# PartsHunter_Slave.net
KiCad netlist of a schematic drawn in EAGLE
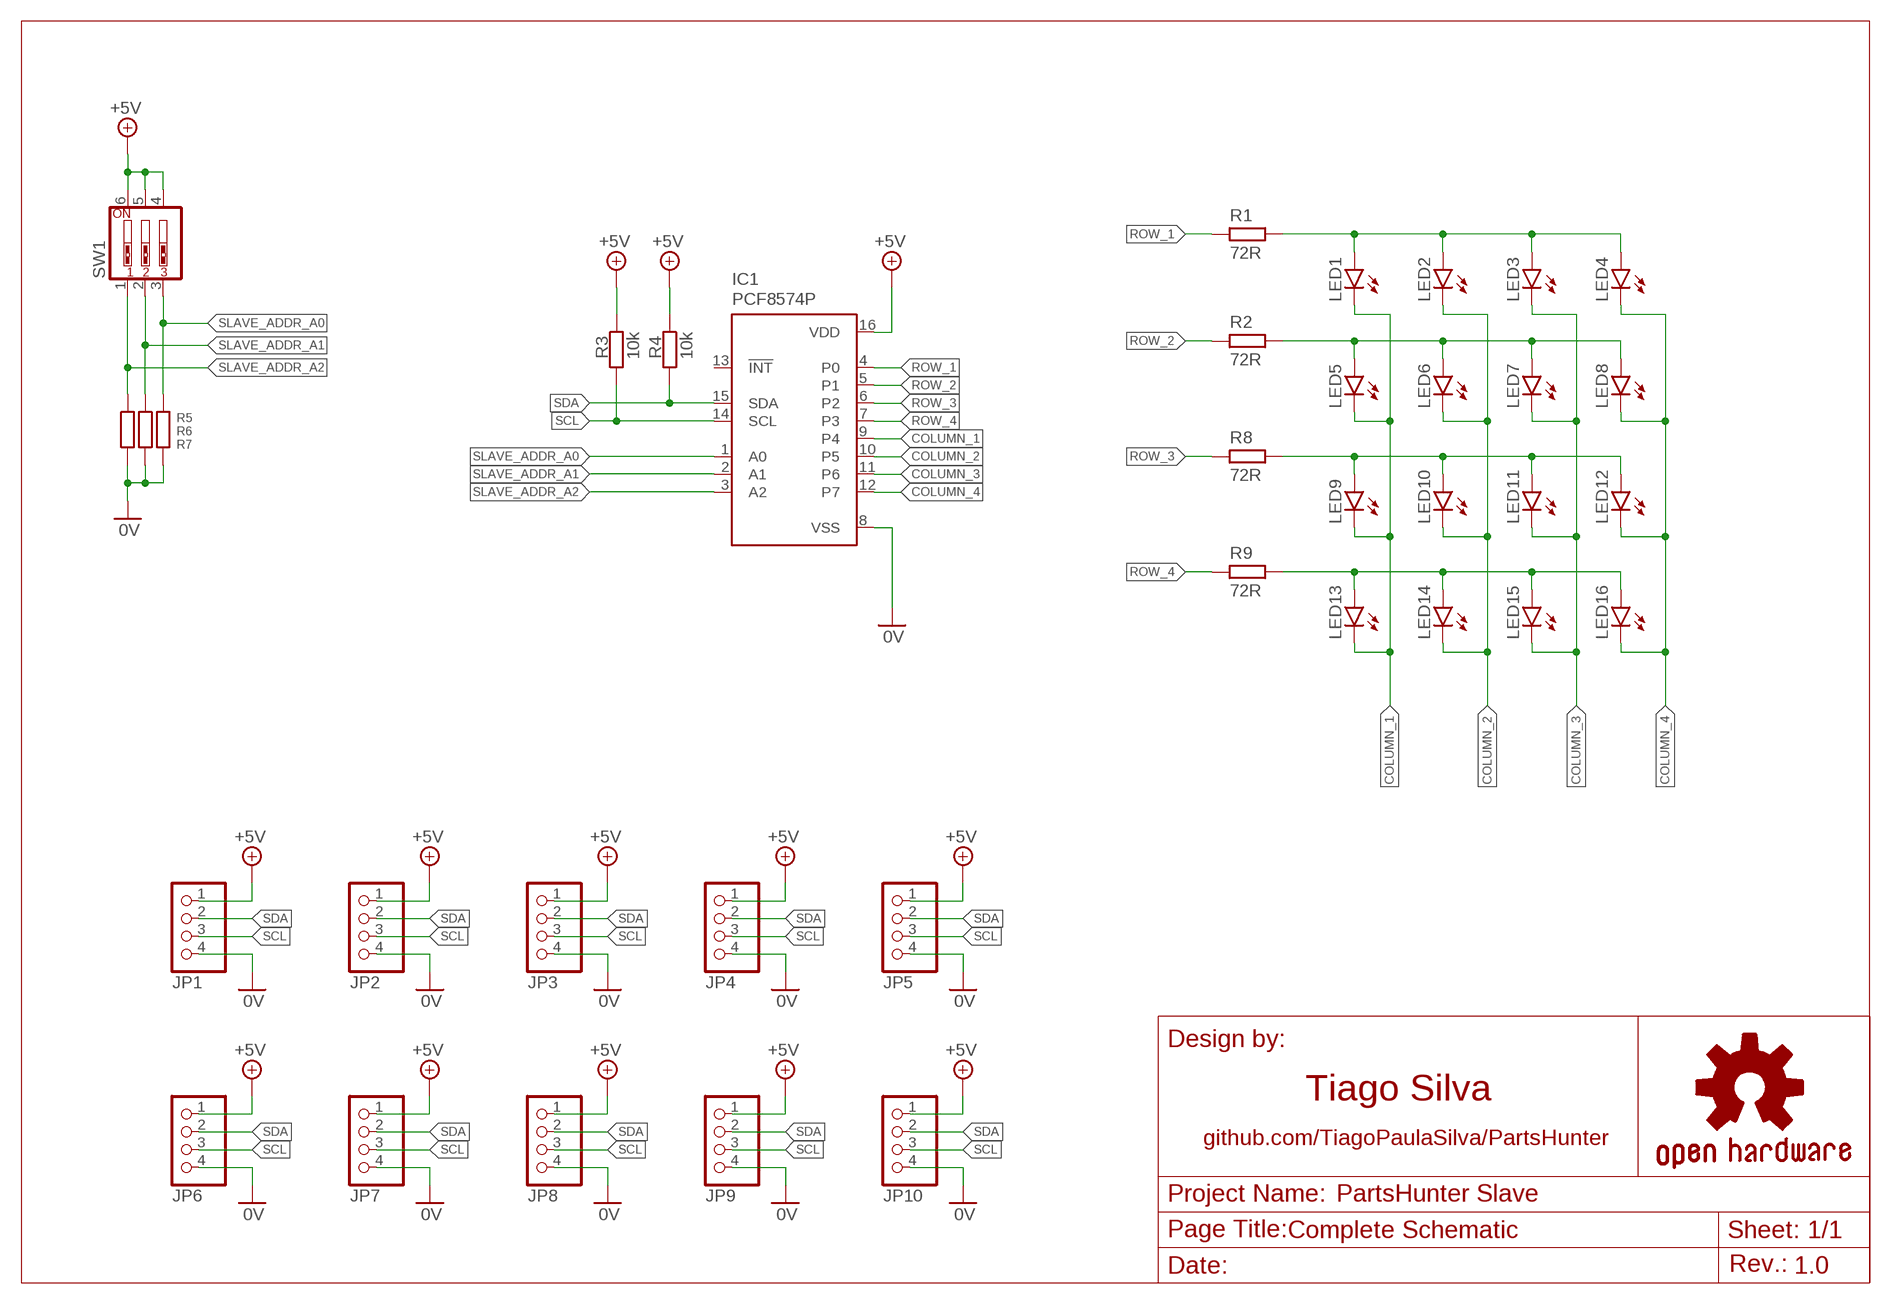
[diagram p0: schematic, sheet 1]

(export (version "E")
  (design (tool "Eeschema 10.0.6"))
  (components
    (comp (ref "IC1")
      (value "PCF8574P")
      (footprint "eagle-import:DIL16")
      (fields (field (name "MPN") "PCF8574PN"))
      (libsource (lib "eagle-import") (part "PCF8574P"))
    )
    (comp (ref "JP1")
      (value "PINHD-1X4/90")
      (footprint "eagle-import:1X04_90")
      (libsource (lib "eagle-import") (part "PINHD-1X4/90"))
    )
    (comp (ref "JP2")
      (value "PINHD-1X4/90")
      (footprint "eagle-import:1X04_90")
      (libsource (lib "eagle-import") (part "PINHD-1X4/90"))
    )
    (comp (ref "JP3")
      (value "PINHD-1X4/90")
      (footprint "eagle-import:1X04_90")
      (libsource (lib "eagle-import") (part "PINHD-1X4/90"))
    )
    (comp (ref "JP4")
      (value "PINHD-1X4/90")
      (footprint "eagle-import:1X04_90")
      (libsource (lib "eagle-import") (part "PINHD-1X4/90"))
    )
    (comp (ref "JP5")
      (value "PINHD-1X4")
      (footprint "eagle-import:1X04")
      (libsource (lib "eagle-import") (part "PINHD-1X4"))
    )
    (comp (ref "JP6")
      (value "PINHD-1X4/90")
      (footprint "eagle-import:1X04_90")
      (libsource (lib "eagle-import") (part "PINHD-1X4/90"))
    )
    (comp (ref "JP7")
      (value "PINHD-1X4/90")
      (footprint "eagle-import:1X04_90")
      (libsource (lib "eagle-import") (part "PINHD-1X4/90"))
    )
    (comp (ref "JP8")
      (value "PINHD-1X4/90")
      (footprint "eagle-import:1X04_90")
      (libsource (lib "eagle-import") (part "PINHD-1X4/90"))
    )
    (comp (ref "JP9")
      (value "PINHD-1X4/90")
      (footprint "eagle-import:1X04_90")
      (libsource (lib "eagle-import") (part "PINHD-1X4/90"))
    )
    (comp (ref "JP10")
      (value "PINHD-1X4")
      (footprint "eagle-import:1X04")
      (libsource (lib "eagle-import") (part "PINHD-1X4"))
    )
    (comp (ref "LED1")
      (value "LEDKA-3528ASYC")
      (footprint "eagle-import:KA-3528ASYC")
      (libsource (lib "eagle-import") (part "LEDKA-3528ASYC"))
    )
    (comp (ref "LED2")
      (value "LEDKA-3528ASYC")
      (footprint "eagle-import:KA-3528ASYC")
      (libsource (lib "eagle-import") (part "LEDKA-3528ASYC"))
    )
    (comp (ref "LED3")
      (value "LEDKA-3528ASYC")
      (footprint "eagle-import:KA-3528ASYC")
      (libsource (lib "eagle-import") (part "LEDKA-3528ASYC"))
    )
    (comp (ref "LED4")
      (value "LEDKA-3528ASYC")
      (footprint "eagle-import:KA-3528ASYC")
      (libsource (lib "eagle-import") (part "LEDKA-3528ASYC"))
    )
    (comp (ref "LED5")
      (value "LEDKA-3528ASYC")
      (footprint "eagle-import:KA-3528ASYC")
      (libsource (lib "eagle-import") (part "LEDKA-3528ASYC"))
    )
    (comp (ref "LED6")
      (value "LEDKA-3528ASYC")
      (footprint "eagle-import:KA-3528ASYC")
      (libsource (lib "eagle-import") (part "LEDKA-3528ASYC"))
    )
    (comp (ref "LED7")
      (value "LEDKA-3528ASYC")
      (footprint "eagle-import:KA-3528ASYC")
      (libsource (lib "eagle-import") (part "LEDKA-3528ASYC"))
    )
    (comp (ref "LED8")
      (value "LEDKA-3528ASYC")
      (footprint "eagle-import:KA-3528ASYC")
      (libsource (lib "eagle-import") (part "LEDKA-3528ASYC"))
    )
    (comp (ref "LED9")
      (value "LEDKA-3528ASYC")
      (footprint "eagle-import:KA-3528ASYC")
      (libsource (lib "eagle-import") (part "LEDKA-3528ASYC"))
    )
    (comp (ref "LED10")
      (value "LEDKA-3528ASYC")
      (footprint "eagle-import:KA-3528ASYC")
      (libsource (lib "eagle-import") (part "LEDKA-3528ASYC"))
    )
    (comp (ref "LED11")
      (value "LEDKA-3528ASYC")
      (footprint "eagle-import:KA-3528ASYC")
      (libsource (lib "eagle-import") (part "LEDKA-3528ASYC"))
    )
    (comp (ref "LED12")
      (value "LEDKA-3528ASYC")
      (footprint "eagle-import:KA-3528ASYC")
      (libsource (lib "eagle-import") (part "LEDKA-3528ASYC"))
    )
    (comp (ref "LED13")
      (value "LEDKA-3528ASYC")
      (footprint "eagle-import:KA-3528ASYC")
      (libsource (lib "eagle-import") (part "LEDKA-3528ASYC"))
    )
    (comp (ref "LED14")
      (value "LEDKA-3528ASYC")
      (footprint "eagle-import:KA-3528ASYC")
      (libsource (lib "eagle-import") (part "LEDKA-3528ASYC"))
    )
    (comp (ref "LED15")
      (value "LEDKA-3528ASYC")
      (footprint "eagle-import:KA-3528ASYC")
      (libsource (lib "eagle-import") (part "LEDKA-3528ASYC"))
    )
    (comp (ref "LED16")
      (value "LEDKA-3528ASYC")
      (footprint "eagle-import:KA-3528ASYC")
      (libsource (lib "eagle-import") (part "LEDKA-3528ASYC"))
    )
    (comp (ref "R1")
      (value "72R")
      (footprint "eagle-import:R0805")
      (libsource (lib "eagle-import") (part "R-EU_R0805"))
    )
    (comp (ref "R2")
      (value "72R")
      (footprint "eagle-import:R0805")
      (libsource (lib "eagle-import") (part "R-EU_R0805"))
    )
    (comp (ref "R3")
      (value "10k")
      (footprint "eagle-import:R0805")
      (libsource (lib "eagle-import") (part "R-EU_R0805"))
    )
    (comp (ref "R4")
      (value "10k")
      (footprint "eagle-import:R0805")
      (libsource (lib "eagle-import") (part "R-EU_R0805"))
    )
    (comp (ref "R5")
      (value "10k")
      (footprint "eagle-import:R0805")
      (libsource (lib "eagle-import") (part "R-EU_R0805"))
    )
    (comp (ref "R6")
      (value "10k")
      (footprint "eagle-import:R0805")
      (libsource (lib "eagle-import") (part "R-EU_R0805"))
    )
    (comp (ref "R7")
      (value "10k")
      (footprint "eagle-import:R0805")
      (libsource (lib "eagle-import") (part "R-EU_R0805"))
    )
    (comp (ref "R8")
      (value "72R")
      (footprint "eagle-import:R0805")
      (libsource (lib "eagle-import") (part "R-EU_R0805"))
    )
    (comp (ref "R9")
      (value "72R")
      (footprint "eagle-import:R0805")
      (libsource (lib "eagle-import") (part "R-EU_R0805"))
    )
    (comp (ref "SW1")
      (value "SW_DIP-3")
      (footprint "eagle-import:EDG-03")
      (libsource (lib "eagle-import") (part "SW_DIP-3"))
    )
  )
  (nets
    (net (code "1") (name "+5V") (class "Default")
      (node (ref "IC1") (pin "16") (pinfunction "VDD_16") (pintype "power_in"))
      (node (ref "JP1") (pin "1") (pinfunction "1_1") (pintype "passive"))
      (node (ref "JP10") (pin "1") (pinfunction "1_1") (pintype "passive"))
      (node (ref "JP2") (pin "1") (pinfunction "1_1") (pintype "passive"))
      (node (ref "JP3") (pin "1") (pinfunction "1_1") (pintype "passive"))
      (node (ref "JP4") (pin "1") (pinfunction "1_1") (pintype "passive"))
      (node (ref "JP5") (pin "1") (pinfunction "1_1") (pintype "passive"))
      (node (ref "JP6") (pin "1") (pinfunction "1_1") (pintype "passive"))
      (node (ref "JP7") (pin "1") (pinfunction "1_1") (pintype "passive"))
      (node (ref "JP8") (pin "1") (pinfunction "1_1") (pintype "passive"))
      (node (ref "JP9") (pin "1") (pinfunction "1_1") (pintype "passive"))
      (node (ref "R3") (pin "1") (pinfunction "1_1") (pintype "passive"))
      (node (ref "R4") (pin "1") (pinfunction "1_1") (pintype "passive"))
      (node (ref "SW1") (pin "4") (pinfunction "4_4") (pintype "passive"))
      (node (ref "SW1") (pin "5") (pinfunction "5_5") (pintype "passive"))
      (node (ref "SW1") (pin "6") (pinfunction "6_6") (pintype "passive"))
    )
    (net (code "2") (name "0V") (class "Default")
      (node (ref "IC1") (pin "8") (pinfunction "VSS_8") (pintype "power_in"))
      (node (ref "JP1") (pin "4") (pinfunction "4_4") (pintype "passive"))
      (node (ref "JP10") (pin "4") (pinfunction "4_4") (pintype "passive"))
      (node (ref "JP2") (pin "4") (pinfunction "4_4") (pintype "passive"))
      (node (ref "JP3") (pin "4") (pinfunction "4_4") (pintype "passive"))
      (node (ref "JP4") (pin "4") (pinfunction "4_4") (pintype "passive"))
      (node (ref "JP5") (pin "4") (pinfunction "4_4") (pintype "passive"))
      (node (ref "JP6") (pin "4") (pinfunction "4_4") (pintype "passive"))
      (node (ref "JP7") (pin "4") (pinfunction "4_4") (pintype "passive"))
      (node (ref "JP8") (pin "4") (pinfunction "4_4") (pintype "passive"))
      (node (ref "JP9") (pin "4") (pinfunction "4_4") (pintype "passive"))
      (node (ref "R5") (pin "2") (pinfunction "2_2") (pintype "passive"))
      (node (ref "R6") (pin "2") (pinfunction "2_2") (pintype "passive"))
      (node (ref "R7") (pin "2") (pinfunction "2_2") (pintype "passive"))
    )
    (net (code "3") (name "COLUMN_1") (class "Default")
      (node (ref "IC1") (pin "9") (pinfunction "P4_9") (pintype "bidirectional"))
      (node (ref "LED1") (pin "C") (pinfunction "C_C") (pintype "passive"))
      (node (ref "LED13") (pin "C") (pinfunction "C_C") (pintype "passive"))
      (node (ref "LED5") (pin "C") (pinfunction "C_C") (pintype "passive"))
      (node (ref "LED9") (pin "C") (pinfunction "C_C") (pintype "passive"))
    )
    (net (code "4") (name "COLUMN_2") (class "Default")
      (node (ref "IC1") (pin "10") (pinfunction "P5_10") (pintype "bidirectional"))
      (node (ref "LED10") (pin "C") (pinfunction "C_C") (pintype "passive"))
      (node (ref "LED14") (pin "C") (pinfunction "C_C") (pintype "passive"))
      (node (ref "LED2") (pin "C") (pinfunction "C_C") (pintype "passive"))
      (node (ref "LED6") (pin "C") (pinfunction "C_C") (pintype "passive"))
    )
    (net (code "5") (name "COLUMN_3") (class "Default")
      (node (ref "IC1") (pin "11") (pinfunction "P6_11") (pintype "bidirectional"))
      (node (ref "LED11") (pin "C") (pinfunction "C_C") (pintype "passive"))
      (node (ref "LED15") (pin "C") (pinfunction "C_C") (pintype "passive"))
      (node (ref "LED3") (pin "C") (pinfunction "C_C") (pintype "passive"))
      (node (ref "LED7") (pin "C") (pinfunction "C_C") (pintype "passive"))
    )
    (net (code "6") (name "COLUMN_4") (class "Default")
      (node (ref "IC1") (pin "12") (pinfunction "P7_12") (pintype "bidirectional"))
      (node (ref "LED12") (pin "C") (pinfunction "C_C") (pintype "passive"))
      (node (ref "LED16") (pin "C") (pinfunction "C_C") (pintype "passive"))
      (node (ref "LED4") (pin "C") (pinfunction "C_C") (pintype "passive"))
      (node (ref "LED8") (pin "C") (pinfunction "C_C") (pintype "passive"))
    )
    (net (code "7") (name "Net-(LED1-PadA)") (class "Default")
      (node (ref "LED1") (pin "A") (pinfunction "A_A") (pintype "passive"))
      (node (ref "LED2") (pin "A") (pinfunction "A_A") (pintype "passive"))
      (node (ref "LED3") (pin "A") (pinfunction "A_A") (pintype "passive"))
      (node (ref "LED4") (pin "A") (pinfunction "A_A") (pintype "passive"))
      (node (ref "R1") (pin "1") (pinfunction "1_1") (pintype "passive"))
    )
    (net (code "8") (name "Net-(LED5-PadA)") (class "Default")
      (node (ref "LED5") (pin "A") (pinfunction "A_A") (pintype "passive"))
      (node (ref "LED6") (pin "A") (pinfunction "A_A") (pintype "passive"))
      (node (ref "LED7") (pin "A") (pinfunction "A_A") (pintype "passive"))
      (node (ref "LED8") (pin "A") (pinfunction "A_A") (pintype "passive"))
      (node (ref "R2") (pin "1") (pinfunction "1_1") (pintype "passive"))
    )
    (net (code "9") (name "Net-(LED10-PadA)") (class "Default")
      (node (ref "LED10") (pin "A") (pinfunction "A_A") (pintype "passive"))
      (node (ref "LED11") (pin "A") (pinfunction "A_A") (pintype "passive"))
      (node (ref "LED12") (pin "A") (pinfunction "A_A") (pintype "passive"))
      (node (ref "LED9") (pin "A") (pinfunction "A_A") (pintype "passive"))
      (node (ref "R8") (pin "1") (pinfunction "1_1") (pintype "passive"))
    )
    (net (code "10") (name "Net-(LED13-PadA)") (class "Default")
      (node (ref "LED13") (pin "A") (pinfunction "A_A") (pintype "passive"))
      (node (ref "LED14") (pin "A") (pinfunction "A_A") (pintype "passive"))
      (node (ref "LED15") (pin "A") (pinfunction "A_A") (pintype "passive"))
      (node (ref "LED16") (pin "A") (pinfunction "A_A") (pintype "passive"))
      (node (ref "R9") (pin "1") (pinfunction "1_1") (pintype "passive"))
    )
    (net (code "11") (name "ROW_1") (class "Default")
      (node (ref "IC1") (pin "4") (pinfunction "P0_4") (pintype "bidirectional"))
      (node (ref "R1") (pin "2") (pinfunction "2_2") (pintype "passive"))
    )
    (net (code "12") (name "ROW_2") (class "Default")
      (node (ref "IC1") (pin "5") (pinfunction "P1_5") (pintype "bidirectional"))
      (node (ref "R2") (pin "2") (pinfunction "2_2") (pintype "passive"))
    )
    (net (code "13") (name "ROW_3") (class "Default")
      (node (ref "IC1") (pin "6") (pinfunction "P2_6") (pintype "bidirectional"))
      (node (ref "R8") (pin "2") (pinfunction "2_2") (pintype "passive"))
    )
    (net (code "14") (name "ROW_4") (class "Default")
      (node (ref "IC1") (pin "7") (pinfunction "P3_7") (pintype "bidirectional"))
      (node (ref "R9") (pin "2") (pinfunction "2_2") (pintype "passive"))
    )
    (net (code "15") (name "SCL") (class "Default")
      (node (ref "IC1") (pin "14") (pinfunction "SCL_14") (pintype "input"))
      (node (ref "JP1") (pin "3") (pinfunction "3_3") (pintype "passive"))
      (node (ref "JP10") (pin "3") (pinfunction "3_3") (pintype "passive"))
      (node (ref "JP2") (pin "3") (pinfunction "3_3") (pintype "passive"))
      (node (ref "JP3") (pin "3") (pinfunction "3_3") (pintype "passive"))
      (node (ref "JP4") (pin "3") (pinfunction "3_3") (pintype "passive"))
      (node (ref "JP5") (pin "3") (pinfunction "3_3") (pintype "passive"))
      (node (ref "JP6") (pin "3") (pinfunction "3_3") (pintype "passive"))
      (node (ref "JP7") (pin "3") (pinfunction "3_3") (pintype "passive"))
      (node (ref "JP8") (pin "3") (pinfunction "3_3") (pintype "passive"))
      (node (ref "JP9") (pin "3") (pinfunction "3_3") (pintype "passive"))
      (node (ref "R3") (pin "2") (pinfunction "2_2") (pintype "passive"))
    )
    (net (code "16") (name "SDA") (class "Default")
      (node (ref "IC1") (pin "15") (pinfunction "SDA_15") (pintype "bidirectional"))
      (node (ref "JP1") (pin "2") (pinfunction "2_2") (pintype "passive"))
      (node (ref "JP10") (pin "2") (pinfunction "2_2") (pintype "passive"))
      (node (ref "JP2") (pin "2") (pinfunction "2_2") (pintype "passive"))
      (node (ref "JP3") (pin "2") (pinfunction "2_2") (pintype "passive"))
      (node (ref "JP4") (pin "2") (pinfunction "2_2") (pintype "passive"))
      (node (ref "JP5") (pin "2") (pinfunction "2_2") (pintype "passive"))
      (node (ref "JP6") (pin "2") (pinfunction "2_2") (pintype "passive"))
      (node (ref "JP7") (pin "2") (pinfunction "2_2") (pintype "passive"))
      (node (ref "JP8") (pin "2") (pinfunction "2_2") (pintype "passive"))
      (node (ref "JP9") (pin "2") (pinfunction "2_2") (pintype "passive"))
      (node (ref "R4") (pin "2") (pinfunction "2_2") (pintype "passive"))
    )
    (net (code "17") (name "SLAVE_ADDR_A0") (class "Default")
      (node (ref "IC1") (pin "1") (pinfunction "A0_1") (pintype "input"))
      (node (ref "R7") (pin "1") (pinfunction "1_1") (pintype "passive"))
      (node (ref "SW1") (pin "3") (pinfunction "3_3") (pintype "passive"))
    )
    (net (code "18") (name "SLAVE_ADDR_A1") (class "Default")
      (node (ref "IC1") (pin "2") (pinfunction "A1_2") (pintype "input"))
      (node (ref "R6") (pin "1") (pinfunction "1_1") (pintype "passive"))
      (node (ref "SW1") (pin "2") (pinfunction "2_2") (pintype "passive"))
    )
    (net (code "19") (name "SLAVE_ADDR_A2") (class "Default")
      (node (ref "IC1") (pin "3") (pinfunction "A2_3") (pintype "input"))
      (node (ref "R5") (pin "1") (pinfunction "1_1") (pintype "passive"))
      (node (ref "SW1") (pin "1") (pinfunction "1_1") (pintype "passive"))
    )
    (net (code "20") (name "unconnected-(IC1-~{INT}-Pad13)") (class "Default")
      (node (ref "IC1") (pin "13") (pinfunction "~{INT}_13") (pintype "output"))
    )
  )
)
